# Batt_Light_2.net
KiCad netlist of a schematic drawn in EAGLE
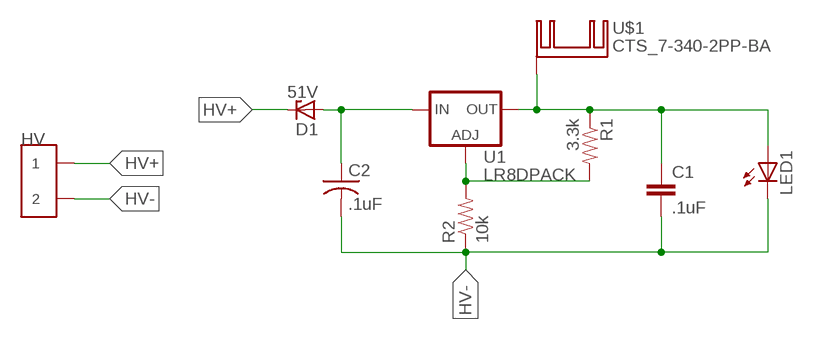
[diagram p0: schematic, sheet 1]

(export (version "E")
  (design (tool "Eeschema 10.0.6"))
  (components
    (comp (ref "C1")
      (value ".1uF")
      (footprint "eagle-import:0603-CAP")
      (libsource (lib "eagle-import") (part "CAP0603-CAP"))
    )
    (comp (ref "C2")
      (value ".1uF")
      (footprint "eagle-import:C2220")
      (libsource (lib "eagle-import") (part "C-USC2220"))
    )
    (comp (ref "D1")
      (value "51V")
      (footprint "eagle-import:SOT23")
      (libsource (lib "eagle-import") (part "ZENER-DIODESOT23"))
    )
    (comp (ref "HV")
      (value "CONN_2")
      (footprint "eagle-import:CONNECTOR_2")
      (libsource (lib "eagle-import") (part "CONN_2"))
    )
    (comp (ref "LED1")
      (value "LEDSMT1206")
      (footprint "eagle-import:1206")
      (libsource (lib "eagle-import") (part "LEDSMT1206"))
    )
    (comp (ref "R1")
      (value "3.3k")
      (footprint "eagle-import:0603-RES")
      (libsource (lib "eagle-import") (part "RESISTOR0603"))
    )
    (comp (ref "R2")
      (value "10k")
      (footprint "eagle-import:0603-RES")
      (libsource (lib "eagle-import") (part "RESISTOR0603"))
    )
    (comp (ref "U$1")
      (value "CTS_7-340-2PP-BA")
      (footprint "eagle-import:TO-200_DUAL")
      (libsource (lib "eagle-import") (part "CTS_7-340-2PP-BA"))
    )
    (comp (ref "U1")
      (value "LR8DPACK")
      (footprint "eagle-import:DPACK")
      (libsource (lib "eagle-import") (part "LR8DPACK"))
    )
  )
  (nets
    (net (code "1") (name "HV+") (class "Default")
      (node (ref "D1") (pin "3") (pinfunction "C_3") (pintype "passive"))
      (node (ref "HV") (pin "1") (pinfunction "1_1") (pintype "bidirectional"))
      (node (ref "HV") (pin "2") (pinfunction "1_2") (pintype "bidirectional"))
    )
    (net (code "2") (name "HV-") (class "Default")
      (node (ref "C1") (pin "2") (pinfunction "2_2") (pintype "passive"))
      (node (ref "C2") (pin "2") (pinfunction "2_2") (pintype "passive"))
      (node (ref "HV") (pin "3") (pinfunction "2_3") (pintype "bidirectional"))
      (node (ref "HV") (pin "4") (pinfunction "2_4") (pintype "bidirectional"))
      (node (ref "LED1") (pin "C") (pinfunction "C_C") (pintype "passive"))
      (node (ref "R2") (pin "1") (pinfunction "1_1") (pintype "passive"))
    )
    (net (code "3") (name "Net-(D1-A)") (class "Default")
      (node (ref "C2") (pin "1") (pinfunction "1_1") (pintype "passive"))
      (node (ref "D1") (pin "1") (pinfunction "A_1") (pintype "passive"))
      (node (ref "U1") (pin "1") (pinfunction "IN_1") (pintype "input"))
    )
    (net (code "4") (name "Net-(U1-ADJ)") (class "Default")
      (node (ref "R1") (pin "2") (pinfunction "2_2") (pintype "passive"))
      (node (ref "R2") (pin "2") (pinfunction "2_2") (pintype "passive"))
      (node (ref "U1") (pin "3") (pinfunction "ADJ_3") (pintype "input"))
    )
    (net (code "5") (name "Net-(U1-OUT)") (class "Default")
      (node (ref "C1") (pin "1") (pinfunction "1_1") (pintype "passive"))
      (node (ref "LED1") (pin "A") (pinfunction "A_A") (pintype "passive"))
      (node (ref "R1") (pin "1") (pinfunction "1_1") (pintype "passive"))
      (node (ref "U$1") (pin "P$1") (pinfunction "K_P$1") (pintype "passive"))
      (node (ref "U$1") (pin "P$2") (pinfunction "K_P$2") (pintype "passive"))
      (node (ref "U$1") (pin "P$3") (pinfunction "K_P$3") (pintype "passive"))
      (node (ref "U1") (pin "4") (pinfunction "OUT_4") (pintype "passive"))
    )
  )
)
